# Qwiic_IMU_Bonobo.net
KiCad netlist of a schematic drawn in EAGLE
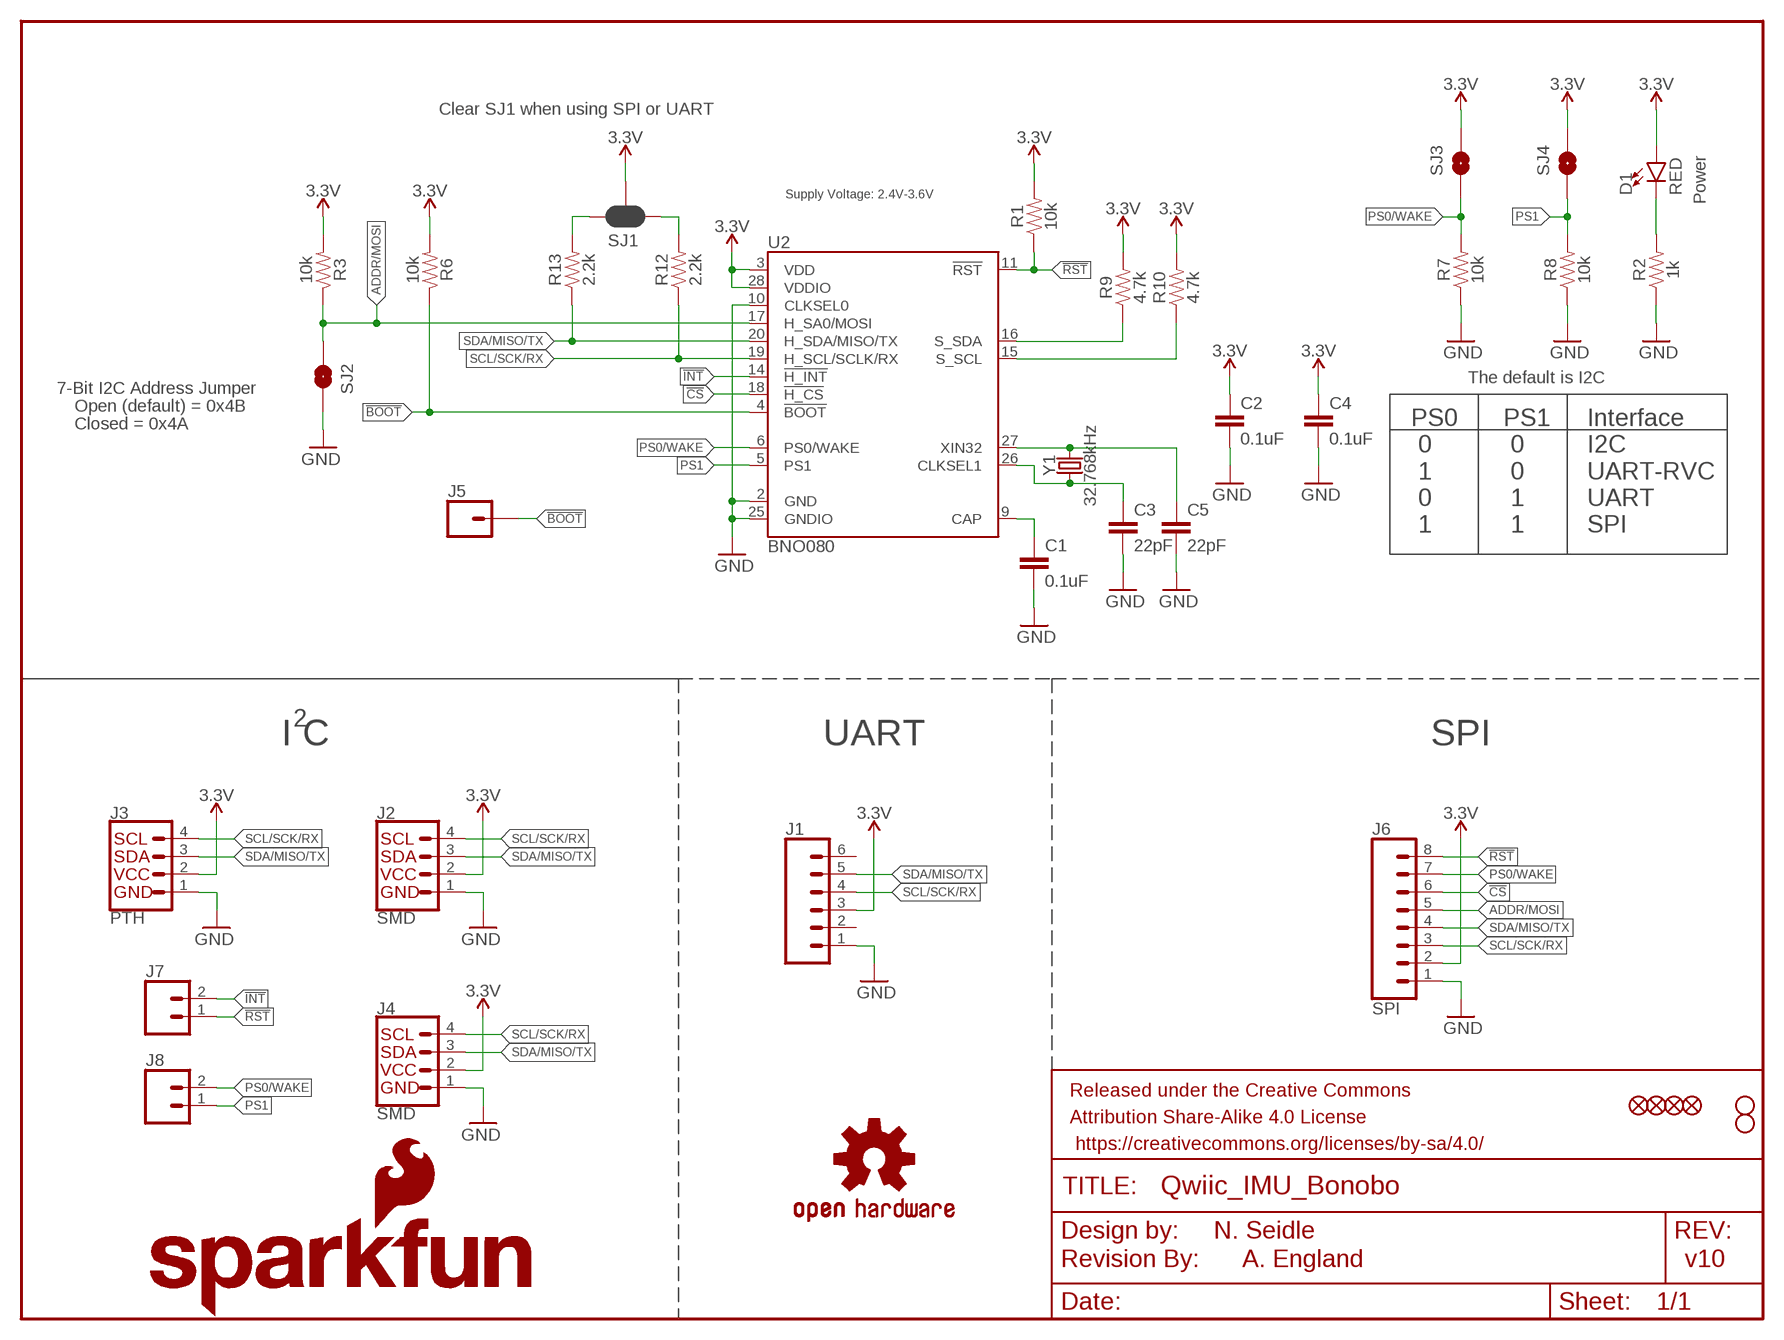
[diagram p0: schematic, sheet 1]

(export (version "E")
  (design (tool "Eeschema 10.0.6"))
  (components
    (comp (ref "C1")
      (value "0.1uF")
      (footprint "eagle-import:0603")
      (libsource (lib "eagle-import") (part "0.1UF-0603-25V-(+80/-20%)"))
    )
    (comp (ref "C2")
      (value "0.1uF")
      (footprint "eagle-import:0603")
      (libsource (lib "eagle-import") (part "0.1UF-0603-25V-(+80/-20%)"))
    )
    (comp (ref "C3")
      (value "22pF")
      (footprint "eagle-import:0603")
      (libsource (lib "eagle-import") (part "22PF-0603-50V-5%"))
    )
    (comp (ref "C4")
      (value "0.1uF")
      (footprint "eagle-import:0603")
      (libsource (lib "eagle-import") (part "0.1UF-0603-25V-(+80/-20%)"))
    )
    (comp (ref "C5")
      (value "22pF")
      (footprint "eagle-import:0603")
      (libsource (lib "eagle-import") (part "22PF-0603-50V-5%"))
    )
    (comp (ref "D1")
      (value "RED")
      (footprint "eagle-import:LED-0603")
      (libsource (lib "eagle-import") (part "LED-RED0603"))
    )
    (comp (ref "FRAME1")
      (value "FRAME-LETTER")
      (footprint "eagle-import:CREATIVE_COMMONS")
      (libsource (lib "eagle-import") (part "FRAME-LETTER"))
    )
    (comp (ref "J1")
      (value "CONN_06NO_SILK_FEMALE_PTH")
      (footprint "eagle-import:1X06_NO_SILK")
      (libsource (lib "eagle-import") (part "CONN_06NO_SILK_FEMALE_PTH"))
    )
    (comp (ref "J2")
      (value "SMD")
      (footprint "eagle-import:1X04_1MM_RA")
      (libsource (lib "eagle-import") (part "I2C_STANDARDJS-1MM"))
    )
    (comp (ref "J3")
      (value "PTH")
      (footprint "eagle-import:1X04_NO_SILK")
      (libsource (lib "eagle-import") (part "I2C_STANDARD_NO_SILK"))
    )
    (comp (ref "J4")
      (value "SMD")
      (footprint "eagle-import:1X04_1MM_RA")
      (libsource (lib "eagle-import") (part "I2C_STANDARDJS-1MM"))
    )
    (comp (ref "J5")
      (value "CONN_01PTH_NO_SILK_YES_STOP")
      (footprint "eagle-import:1X01_NO_SILK")
      (libsource (lib "eagle-import") (part "CONN_01PTH_NO_SILK_YES_STOP"))
    )
    (comp (ref "J6")
      (value "SPI")
      (footprint "eagle-import:1X08_NO_SILK")
      (libsource (lib "eagle-import") (part "CONN_08NO_SILK_FEMALE_PTH"))
    )
    (comp (ref "J7")
      (value "CONN_021X02_NO_SILK")
      (footprint "eagle-import:1X02_NO_SILK")
      (libsource (lib "eagle-import") (part "CONN_021X02_NO_SILK"))
    )
    (comp (ref "J8")
      (value "CONN_021X02_NO_SILK")
      (footprint "eagle-import:1X02_NO_SILK")
      (libsource (lib "eagle-import") (part "CONN_021X02_NO_SILK"))
    )
    (comp (ref "JP1")
      (value "FIDUCIALUFIDUCIAL")
      (footprint "eagle-import:MICRO-FIDUCIAL")
      (libsource (lib "eagle-import") (part "FIDUCIALUFIDUCIAL"))
    )
    (comp (ref "JP2")
      (value "FIDUCIALUFIDUCIAL")
      (footprint "eagle-import:MICRO-FIDUCIAL")
      (libsource (lib "eagle-import") (part "FIDUCIALUFIDUCIAL"))
    )
    (comp (ref "JP3")
      (value "STAND-OFF")
      (footprint "eagle-import:STAND-OFF")
      (libsource (lib "eagle-import") (part "STAND-OFF"))
    )
    (comp (ref "JP4")
      (value "STAND-OFF")
      (footprint "eagle-import:STAND-OFF")
      (libsource (lib "eagle-import") (part "STAND-OFF"))
    )
    (comp (ref "JP5")
      (value "FIDUCIALUFIDUCIAL")
      (footprint "eagle-import:MICRO-FIDUCIAL")
      (libsource (lib "eagle-import") (part "FIDUCIALUFIDUCIAL"))
    )
    (comp (ref "JP6")
      (value "FIDUCIALUFIDUCIAL")
      (footprint "eagle-import:MICRO-FIDUCIAL")
      (libsource (lib "eagle-import") (part "FIDUCIALUFIDUCIAL"))
    )
    (comp (ref "LOGO1")
      (value "OSHW-LOGOMINI")
      (footprint "eagle-import:OSHW-LOGO-MINI")
      (libsource (lib "eagle-import") (part "OSHW-LOGOMINI"))
    )
    (comp (ref "LOGO2")
      (value "REVISION")
      (footprint "eagle-import:REVISION")
      (libsource (lib "eagle-import") (part "REVISION"))
    )
    (comp (ref "LOGO4")
      (value "SFE_LOGO_FLAME.1_INCH")
      (footprint "eagle-import:SFE_LOGO_FLAME_.1")
      (libsource (lib "eagle-import") (part "SFE_LOGO_FLAME.1_INCH"))
    )
    (comp (ref "LOGO5")
      (value "SFE_LOGO_NAME_FLAME.1_INCH")
      (footprint "eagle-import:SFE_LOGO_NAME_FLAME_.1")
      (libsource (lib "eagle-import") (part "SFE_LOGO_NAME_FLAME.1_INCH"))
    )
    (comp (ref "R1")
      (value "10k")
      (footprint "eagle-import:0603")
      (libsource (lib "eagle-import") (part "10KOHM-0603-1/10W-1%"))
    )
    (comp (ref "R2")
      (value "1k")
      (footprint "eagle-import:0603")
      (libsource (lib "eagle-import") (part "1KOHM-0603-1/10W-1%"))
    )
    (comp (ref "R3")
      (value "10k")
      (footprint "eagle-import:0603")
      (libsource (lib "eagle-import") (part "10KOHM-0603-1/10W-1%"))
    )
    (comp (ref "R6")
      (value "10k")
      (footprint "eagle-import:0603")
      (libsource (lib "eagle-import") (part "10KOHM-0603-1/10W-1%"))
    )
    (comp (ref "R7")
      (value "10k")
      (footprint "eagle-import:0603")
      (libsource (lib "eagle-import") (part "10KOHM-0603-1/10W-1%"))
    )
    (comp (ref "R8")
      (value "10k")
      (footprint "eagle-import:0603")
      (libsource (lib "eagle-import") (part "10KOHM-0603-1/10W-1%"))
    )
    (comp (ref "R9")
      (value "4.7k")
      (footprint "eagle-import:0603")
      (libsource (lib "eagle-import") (part "4.7KOHM-0603-1/10W-1%"))
    )
    (comp (ref "R10")
      (value "4.7k")
      (footprint "eagle-import:0603")
      (libsource (lib "eagle-import") (part "4.7KOHM-0603-1/10W-1%"))
    )
    (comp (ref "R12")
      (value "2.2k")
      (footprint "eagle-import:0603")
      (libsource (lib "eagle-import") (part "2.2KOHM-0603-1/10W-1%"))
    )
    (comp (ref "R13")
      (value "2.2k")
      (footprint "eagle-import:0603")
      (libsource (lib "eagle-import") (part "2.2KOHM-0603-1/10W-1%"))
    )
    (comp (ref "SJ1")
      (value "JUMPER-SMT_3_2-NC_PASTE_SILK")
      (footprint "eagle-import:SMT-JUMPER_3_2-NC_PASTE_SILK")
      (libsource (lib "eagle-import") (part "JUMPER-SMT_3_2-NC_PASTE_SILK"))
    )
    (comp (ref "SJ2")
      (value "SOLDERJUMPERNO")
      (footprint "eagle-import:SJ_2S-NO")
      (libsource (lib "eagle-import") (part "SOLDERJUMPERNO"))
    )
    (comp (ref "SJ3")
      (value "SOLDERJUMPERNO")
      (footprint "eagle-import:SJ_2S-NO")
      (libsource (lib "eagle-import") (part "SOLDERJUMPERNO"))
    )
    (comp (ref "SJ4")
      (value "SOLDERJUMPERNO")
      (footprint "eagle-import:SJ_2S-NO")
      (libsource (lib "eagle-import") (part "SOLDERJUMPERNO"))
    )
    (comp (ref "U2")
      (value "BNO080")
      (footprint "eagle-import:LGA-28")
      (libsource (lib "eagle-import") (part "BNO080"))
    )
    (comp (ref "Y1")
      (value "32.768kHz")
      (footprint "eagle-import:CRYSTAL-SMD-3.2X1.5MM")
      (libsource (lib "eagle-import") (part "CRYSTAL-32.768KHZSMD-3.2X1.5"))
    )
  )
  (nets
    (net (code "1") (name "/~{BOOT}") (class "Default")
      (node (ref "J5") (pin "1") (pinfunction "1_1") (pintype "passive"))
      (node (ref "R6") (pin "1") (pinfunction "1_1") (pintype "passive"))
      (node (ref "U2") (pin "4") (pinfunction "~{BOOT}_4") (pintype "bidirectional"))
    )
    (net (code "2") (name "/~{CS}") (class "Default")
      (node (ref "J6") (pin "6") (pinfunction "6_6") (pintype "passive"))
      (node (ref "U2") (pin "18") (pinfunction "~{H_CS}_18") (pintype "bidirectional"))
    )
    (net (code "3") (name "/~{INT}") (class "Default")
      (node (ref "J7") (pin "2") (pinfunction "2_2") (pintype "passive"))
      (node (ref "U2") (pin "14") (pinfunction "~{H_INT}_14") (pintype "bidirectional"))
    )
    (net (code "4") (name "/~{RST}") (class "Default")
      (node (ref "J6") (pin "8") (pinfunction "8_8") (pintype "passive"))
      (node (ref "J7") (pin "1") (pinfunction "1_1") (pintype "passive"))
      (node (ref "R1") (pin "1") (pinfunction "1_1") (pintype "passive"))
      (node (ref "U2") (pin "11") (pinfunction "~{RST}_11") (pintype "bidirectional"))
    )
    (net (code "5") (name "3.3V") (class "Default")
      (node (ref "C2") (pin "1") (pinfunction "1_1") (pintype "passive"))
      (node (ref "C4") (pin "1") (pinfunction "1_1") (pintype "passive"))
      (node (ref "D1") (pin "A") (pinfunction "A_A") (pintype "passive"))
      (node (ref "J1") (pin "3") (pinfunction "3_3") (pintype "passive"))
      (node (ref "J2") (pin "2") (pinfunction "VCC_2") (pintype "power_in"))
      (node (ref "J3") (pin "2") (pinfunction "VCC_2") (pintype "power_in"))
      (node (ref "J4") (pin "2") (pinfunction "VCC_2") (pintype "power_in"))
      (node (ref "J6") (pin "2") (pinfunction "2_2") (pintype "passive"))
      (node (ref "R1") (pin "2") (pinfunction "2_2") (pintype "passive"))
      (node (ref "R10") (pin "2") (pinfunction "2_2") (pintype "passive"))
      (node (ref "R3") (pin "2") (pinfunction "2_2") (pintype "passive"))
      (node (ref "R6") (pin "2") (pinfunction "2_2") (pintype "passive"))
      (node (ref "R9") (pin "2") (pinfunction "2_2") (pintype "passive"))
      (node (ref "SJ1") (pin "2") (pinfunction "2_2") (pintype "passive"))
      (node (ref "SJ3") (pin "1") (pinfunction "1_1") (pintype "passive"))
      (node (ref "SJ4") (pin "1") (pinfunction "1_1") (pintype "passive"))
      (node (ref "U2") (pin "28") (pinfunction "VDDIO_28") (pintype "bidirectional"))
      (node (ref "U2") (pin "3") (pinfunction "VDD_3") (pintype "bidirectional"))
    )
    (net (code "6") (name "ADDR{slash}MOSI") (class "Default")
      (node (ref "J6") (pin "5") (pinfunction "5_5") (pintype "passive"))
      (node (ref "R3") (pin "1") (pinfunction "1_1") (pintype "passive"))
      (node (ref "SJ2") (pin "2") (pinfunction "2_2") (pintype "passive"))
      (node (ref "U2") (pin "17") (pinfunction "H_SA0/MOSI_17") (pintype "bidirectional"))
    )
    (net (code "7") (name "GND") (class "Default")
      (node (ref "C1") (pin "2") (pinfunction "2_2") (pintype "passive"))
      (node (ref "C2") (pin "2") (pinfunction "2_2") (pintype "passive"))
      (node (ref "C3") (pin "2") (pinfunction "2_2") (pintype "passive"))
      (node (ref "C4") (pin "2") (pinfunction "2_2") (pintype "passive"))
      (node (ref "C5") (pin "2") (pinfunction "2_2") (pintype "passive"))
      (node (ref "J1") (pin "1") (pinfunction "1_1") (pintype "passive"))
      (node (ref "J2") (pin "1") (pinfunction "GND_1") (pintype "power_in"))
      (node (ref "J3") (pin "1") (pinfunction "GND_1") (pintype "power_in"))
      (node (ref "J4") (pin "1") (pinfunction "GND_1") (pintype "power_in"))
      (node (ref "J6") (pin "1") (pinfunction "1_1") (pintype "passive"))
      (node (ref "R2") (pin "1") (pinfunction "1_1") (pintype "passive"))
      (node (ref "R7") (pin "1") (pinfunction "1_1") (pintype "passive"))
      (node (ref "R8") (pin "1") (pinfunction "1_1") (pintype "passive"))
      (node (ref "SJ2") (pin "1") (pinfunction "1_1") (pintype "passive"))
      (node (ref "U2") (pin "10") (pinfunction "CLKSEL0_10") (pintype "bidirectional"))
      (node (ref "U2") (pin "2") (pinfunction "GND_2") (pintype "bidirectional"))
      (node (ref "U2") (pin "25") (pinfunction "GNDIO_25") (pintype "bidirectional"))
    )
    (net (code "8") (name "Net-(D1-PadC)") (class "Default")
      (node (ref "D1") (pin "C") (pinfunction "C_C") (pintype "passive"))
      (node (ref "R2") (pin "2") (pinfunction "2_2") (pintype "passive"))
    )
    (net (code "9") (name "Net-(R12-Pad2)") (class "Default")
      (node (ref "R12") (pin "2") (pinfunction "2_2") (pintype "passive"))
      (node (ref "SJ1") (pin "1") (pinfunction "1_1") (pintype "passive"))
    )
    (net (code "10") (name "Net-(R13-Pad2)") (class "Default")
      (node (ref "R13") (pin "2") (pinfunction "2_2") (pintype "passive"))
      (node (ref "SJ1") (pin "3") (pinfunction "3_3") (pintype "passive"))
    )
    (net (code "11") (name "Net-(U2-CAP)") (class "Default")
      (node (ref "C1") (pin "1") (pinfunction "1_1") (pintype "passive"))
      (node (ref "U2") (pin "9") (pinfunction "CAP_9") (pintype "bidirectional"))
    )
    (net (code "12") (name "Net-(U2-CLKSEL1)") (class "Default")
      (node (ref "C3") (pin "1") (pinfunction "1_1") (pintype "passive"))
      (node (ref "U2") (pin "26") (pinfunction "CLKSEL1_26") (pintype "bidirectional"))
      (node (ref "Y1") (pin "P$1") (pinfunction "1_P$1") (pintype "passive"))
    )
    (net (code "13") (name "Net-(U2-S_SCL)") (class "Default")
      (node (ref "R10") (pin "1") (pinfunction "1_1") (pintype "passive"))
      (node (ref "U2") (pin "15") (pinfunction "S_SCL_15") (pintype "bidirectional"))
    )
    (net (code "14") (name "Net-(U2-S_SDA)") (class "Default")
      (node (ref "R9") (pin "1") (pinfunction "1_1") (pintype "passive"))
      (node (ref "U2") (pin "16") (pinfunction "S_SDA_16") (pintype "bidirectional"))
    )
    (net (code "15") (name "Net-(U2-XIN32)") (class "Default")
      (node (ref "C5") (pin "1") (pinfunction "1_1") (pintype "passive"))
      (node (ref "U2") (pin "27") (pinfunction "XIN32_27") (pintype "bidirectional"))
      (node (ref "Y1") (pin "P$2") (pinfunction "2_P$2") (pintype "passive"))
    )
    (net (code "16") (name "PS0{slash}WAKE") (class "Default")
      (node (ref "J6") (pin "7") (pinfunction "7_7") (pintype "passive"))
      (node (ref "J8") (pin "2") (pinfunction "2_2") (pintype "passive"))
      (node (ref "R7") (pin "2") (pinfunction "2_2") (pintype "passive"))
      (node (ref "SJ3") (pin "2") (pinfunction "2_2") (pintype "passive"))
      (node (ref "U2") (pin "6") (pinfunction "PS0/WAKE_6") (pintype "bidirectional"))
    )
    (net (code "17") (name "PS1") (class "Default")
      (node (ref "J8") (pin "1") (pinfunction "1_1") (pintype "passive"))
      (node (ref "R8") (pin "2") (pinfunction "2_2") (pintype "passive"))
      (node (ref "SJ4") (pin "2") (pinfunction "2_2") (pintype "passive"))
      (node (ref "U2") (pin "5") (pinfunction "PS1_5") (pintype "bidirectional"))
    )
    (net (code "18") (name "SCL{slash}SCK{slash}RX") (class "Default")
      (node (ref "J1") (pin "4") (pinfunction "4_4") (pintype "passive"))
      (node (ref "J2") (pin "4") (pinfunction "SCL_4") (pintype "passive"))
      (node (ref "J3") (pin "4") (pinfunction "SCL_4") (pintype "passive"))
      (node (ref "J4") (pin "4") (pinfunction "SCL_4") (pintype "passive"))
      (node (ref "J6") (pin "3") (pinfunction "3_3") (pintype "passive"))
      (node (ref "R12") (pin "1") (pinfunction "1_1") (pintype "passive"))
      (node (ref "U2") (pin "19") (pinfunction "H_SCL/SCLK/RX_19") (pintype "bidirectional"))
    )
    (net (code "19") (name "SDA{slash}MISO{slash}TX") (class "Default")
      (node (ref "J1") (pin "5") (pinfunction "5_5") (pintype "passive"))
      (node (ref "J2") (pin "3") (pinfunction "SDA_3") (pintype "passive"))
      (node (ref "J3") (pin "3") (pinfunction "SDA_3") (pintype "passive"))
      (node (ref "J4") (pin "3") (pinfunction "SDA_3") (pintype "passive"))
      (node (ref "J6") (pin "4") (pinfunction "4_4") (pintype "passive"))
      (node (ref "R13") (pin "1") (pinfunction "1_1") (pintype "passive"))
      (node (ref "U2") (pin "20") (pinfunction "H_SDA/MISO/TX_20") (pintype "bidirectional"))
    )
    (net (code "20") (name "unconnected-(J1-Pad2)") (class "Default")
      (node (ref "J1") (pin "2") (pinfunction "2_2") (pintype "passive"))
    )
    (net (code "21") (name "unconnected-(J1-Pad6)") (class "Default")
      (node (ref "J1") (pin "6") (pinfunction "6_6") (pintype "passive"))
    )
  )
)
